# rotary_encoder_4.net
KiCad netlist of a schematic drawn in EAGLE
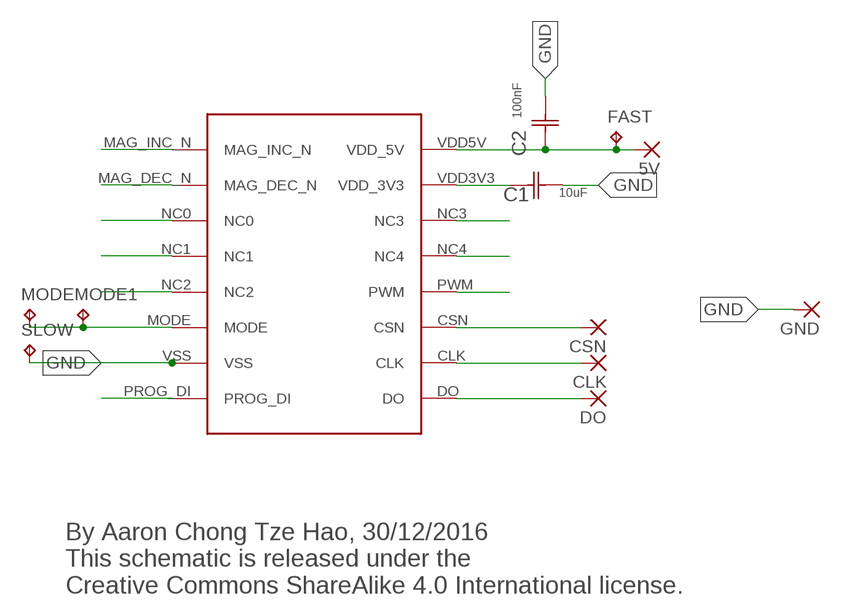
[diagram p0: schematic, sheet 1]

(export (version "E")
  (design (tool "Eeschema 10.0.6"))
  (components
    (comp (ref "5V")
      (value "1,6/0,8")
      (footprint "eagle-import:1,6_0,8")
      (libsource (lib "eagle-import") (part "1,6/0,8"))
    )
    (comp (ref "C1")
      (value "10uF")
      (footprint "eagle-import:CAP_0805_100NF")
      (fields (field (name "MPN") "0805F106Z100CT") (field (name "TOLERANCE") "-20/+80%"))
      (libsource (lib "eagle-import") (part "CAP_0805_10UF"))
    )
    (comp (ref "C2")
      (value "100nF")
      (footprint "eagle-import:CAP_0805_100NF")
      (fields (field (name "MPN") "U0805F104ZCT") (field (name "TOLERANCE") "-20/+80%"))
      (libsource (lib "eagle-import") (part "CAP_0805_100NF"))
    )
    (comp (ref "CLK")
      (value "1,6/0,8")
      (footprint "eagle-import:1,6_0,8")
      (libsource (lib "eagle-import") (part "1,6/0,8"))
    )
    (comp (ref "CSN")
      (value "1,6/0,8")
      (footprint "eagle-import:1,6_0,8")
      (libsource (lib "eagle-import") (part "1,6/0,8"))
    )
    (comp (ref "DO")
      (value "1,6/0,8")
      (footprint "eagle-import:1,6_0,8")
      (libsource (lib "eagle-import") (part "1,6/0,8"))
    )
    (comp (ref "FAST")
      (value "TPTP10SQ")
      (footprint "eagle-import:TP10SQ")
      (libsource (lib "eagle-import") (part "TPTP10SQ"))
    )
    (comp (ref "GND")
      (value "1,6/0,8")
      (footprint "eagle-import:1,6_0,8")
      (libsource (lib "eagle-import") (part "1,6/0,8"))
    )
    (comp (ref "MODE")
      (value "TPTP10SQ")
      (footprint "eagle-import:TP10SQ")
      (libsource (lib "eagle-import") (part "TPTP10SQ"))
    )
    (comp (ref "MODE1")
      (value "TPTP10SQ")
      (footprint "eagle-import:TP10SQ")
      (libsource (lib "eagle-import") (part "TPTP10SQ"))
    )
    (comp (ref "SLOW")
      (value "TPTP10SQ")
      (footprint "eagle-import:TP10SQ")
      (libsource (lib "eagle-import") (part "TPTP10SQ"))
    )
    (comp (ref "U$1")
      (value "AS5045_ROTARY_ENCODER")
      (footprint "eagle-import:AS5045_ROTARY_ENCODER")
      (libsource (lib "eagle-import") (part "AS5045_ROTARY_ENCODER"))
    )
  )
  (nets
    (net (code "1") (name "GND") (class "Default")
      (node (ref "C1") (pin "2") (pinfunction "C2_2") (pintype "passive"))
      (node (ref "C2") (pin "2") (pinfunction "C2_2") (pintype "passive"))
      (node (ref "GND") (pin "1") (pinfunction "P_1") (pintype "passive"))
      (node (ref "SLOW") (pin "TP") (pinfunction "TP_TP") (pintype "input"))
      (node (ref "U$1") (pin "VSS") (pinfunction "VSS_VSS") (pintype "bidirectional"))
    )
    (net (code "2") (name "Net-(5V-P)") (class "Default")
      (node (ref "5V") (pin "1") (pinfunction "P_1") (pintype "passive"))
      (node (ref "C2") (pin "1") (pinfunction "C1_1") (pintype "passive"))
      (node (ref "FAST") (pin "TP") (pinfunction "TP_TP") (pintype "input"))
      (node (ref "U$1") (pin "VDD5V") (pinfunction "VDD_5V_VDD5V") (pintype "bidirectional"))
    )
    (net (code "3") (name "Net-(C1-C1)") (class "Default")
      (node (ref "C1") (pin "1") (pinfunction "C1_1") (pintype "passive"))
      (node (ref "U$1") (pin "VDD3V3") (pinfunction "VDD_3V3_VDD3V3") (pintype "bidirectional"))
    )
    (net (code "4") (name "Net-(CLK-P)") (class "Default")
      (node (ref "CLK") (pin "1") (pinfunction "P_1") (pintype "passive"))
      (node (ref "U$1") (pin "CLK") (pinfunction "CLK_CLK") (pintype "bidirectional"))
    )
    (net (code "5") (name "Net-(CSN-P)") (class "Default")
      (node (ref "CSN") (pin "1") (pinfunction "P_1") (pintype "passive"))
      (node (ref "U$1") (pin "CSN") (pinfunction "CSN_CSN") (pintype "bidirectional"))
    )
    (net (code "6") (name "Net-(DO-P)") (class "Default")
      (node (ref "DO") (pin "1") (pinfunction "P_1") (pintype "passive"))
      (node (ref "U$1") (pin "DO") (pinfunction "DO_DO") (pintype "bidirectional"))
    )
    (net (code "7") (name "Net-(MODE-PadTP)") (class "Default")
      (node (ref "MODE") (pin "TP") (pinfunction "TP_TP") (pintype "input"))
      (node (ref "MODE1") (pin "TP") (pinfunction "TP_TP") (pintype "input"))
      (node (ref "U$1") (pin "MODE") (pinfunction "MODE_MODE") (pintype "bidirectional"))
    )
    (net (code "8") (name "unconnected-(U$1-PadMAG_DEC_N)") (class "Default")
      (node (ref "U$1") (pin "MAG_DEC_N") (pinfunction "MAG_DEC_N_MAG_DEC_N") (pintype "bidirectional"))
    )
    (net (code "9") (name "unconnected-(U$1-PadMAG_INC_N)") (class "Default")
      (node (ref "U$1") (pin "MAG_INC_N") (pinfunction "MAG_INC_N_MAG_INC_N") (pintype "bidirectional"))
    )
    (net (code "10") (name "unconnected-(U$1-PadNC0)") (class "Default")
      (node (ref "U$1") (pin "NC0") (pinfunction "NC0_NC0") (pintype "bidirectional"))
    )
    (net (code "11") (name "unconnected-(U$1-PadNC1)") (class "Default")
      (node (ref "U$1") (pin "NC1") (pinfunction "NC1_NC1") (pintype "bidirectional"))
    )
    (net (code "12") (name "unconnected-(U$1-PadNC2)") (class "Default")
      (node (ref "U$1") (pin "NC2") (pinfunction "NC2_NC2") (pintype "bidirectional"))
    )
    (net (code "13") (name "unconnected-(U$1-PadNC3)") (class "Default")
      (node (ref "U$1") (pin "NC3") (pinfunction "NC3_NC3") (pintype "bidirectional"))
    )
    (net (code "14") (name "unconnected-(U$1-PadNC4)") (class "Default")
      (node (ref "U$1") (pin "NC4") (pinfunction "NC4_NC4") (pintype "bidirectional"))
    )
    (net (code "15") (name "unconnected-(U$1-PadPROG_DI)") (class "Default")
      (node (ref "U$1") (pin "PROG_DI") (pinfunction "PROG_DI_PROG_DI") (pintype "bidirectional"))
    )
    (net (code "16") (name "unconnected-(U$1-PadPWM)") (class "Default")
      (node (ref "U$1") (pin "PWM") (pinfunction "PWM_PWM") (pintype "bidirectional"))
    )
  )
)
